# push_Button.net
KiCad netlist of a schematic drawn in EAGLE
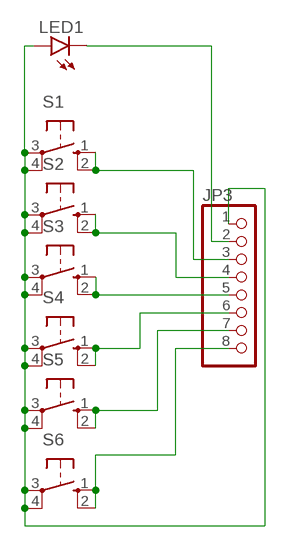
[diagram p0: schematic, sheet 1]

(export (version "E")
  (design (tool "Eeschema 10.0.6"))
  (components
    (comp (ref "JP3")
      (value "PINHD-1X8")
      (footprint "eagle-import:1X08")
      (libsource (lib "eagle-import") (part "PINHD-1X8"))
    )
    (comp (ref "LED1")
      (value "LED5MM")
      (footprint "eagle-import:LED5MM")
      (libsource (lib "eagle-import") (part "LED5MM"))
    )
    (comp (ref "S1")
      (value "10-XX")
      (footprint "eagle-import:B3F-10XX")
      (fields (field (name "MPN") "B3F-1000"))
      (libsource (lib "eagle-import") (part "10-XX"))
    )
    (comp (ref "S2")
      (value "10-XX")
      (footprint "eagle-import:B3F-10XX")
      (fields (field (name "MPN") "B3F-1000"))
      (libsource (lib "eagle-import") (part "10-XX"))
    )
    (comp (ref "S3")
      (value "10-XX")
      (footprint "eagle-import:B3F-10XX")
      (fields (field (name "MPN") "B3F-1000"))
      (libsource (lib "eagle-import") (part "10-XX"))
    )
    (comp (ref "S4")
      (value "10-XX")
      (footprint "eagle-import:B3F-10XX")
      (fields (field (name "MPN") "B3F-1000"))
      (libsource (lib "eagle-import") (part "10-XX"))
    )
    (comp (ref "S5")
      (value "10-XX")
      (footprint "eagle-import:B3F-10XX")
      (fields (field (name "MPN") "B3F-1000"))
      (libsource (lib "eagle-import") (part "10-XX"))
    )
    (comp (ref "S6")
      (value "10-XX")
      (footprint "eagle-import:B3F-10XX")
      (fields (field (name "MPN") "B3F-1000"))
      (libsource (lib "eagle-import") (part "10-XX"))
    )
  )
  (nets
    (net (code "1") (name "Net-(LED1-C)") (class "Default")
      (node (ref "JP3") (pin "2") (pinfunction "2_2") (pintype "passive"))
      (node (ref "LED1") (pin "K") (pinfunction "C_K") (pintype "passive"))
    )
    (net (code "2") (name "Net-(S1-P)") (class "Default")
      (node (ref "JP3") (pin "1") (pinfunction "1_1") (pintype "passive"))
      (node (ref "LED1") (pin "A") (pinfunction "A_A") (pintype "passive"))
      (node (ref "S1") (pin "3") (pinfunction "P_3") (pintype "passive"))
      (node (ref "S1") (pin "4") (pinfunction "P1_4") (pintype "passive"))
      (node (ref "S2") (pin "3") (pinfunction "P_3") (pintype "passive"))
      (node (ref "S2") (pin "4") (pinfunction "P1_4") (pintype "passive"))
      (node (ref "S3") (pin "3") (pinfunction "P_3") (pintype "passive"))
      (node (ref "S3") (pin "4") (pinfunction "P1_4") (pintype "passive"))
      (node (ref "S4") (pin "3") (pinfunction "P_3") (pintype "passive"))
      (node (ref "S4") (pin "4") (pinfunction "P1_4") (pintype "passive"))
      (node (ref "S5") (pin "3") (pinfunction "P_3") (pintype "passive"))
      (node (ref "S5") (pin "4") (pinfunction "P1_4") (pintype "passive"))
      (node (ref "S6") (pin "3") (pinfunction "P_3") (pintype "passive"))
      (node (ref "S6") (pin "4") (pinfunction "P1_4") (pintype "passive"))
    )
    (net (code "3") (name "Net-(S1-S)") (class "Default")
      (node (ref "JP3") (pin "3") (pinfunction "3_3") (pintype "passive"))
      (node (ref "S1") (pin "1") (pinfunction "S_1") (pintype "passive"))
      (node (ref "S1") (pin "2") (pinfunction "S1_2") (pintype "passive"))
    )
    (net (code "4") (name "Net-(S2-S)") (class "Default")
      (node (ref "JP3") (pin "4") (pinfunction "4_4") (pintype "passive"))
      (node (ref "S2") (pin "1") (pinfunction "S_1") (pintype "passive"))
      (node (ref "S2") (pin "2") (pinfunction "S1_2") (pintype "passive"))
    )
    (net (code "5") (name "Net-(S3-S)") (class "Default")
      (node (ref "JP3") (pin "5") (pinfunction "5_5") (pintype "passive"))
      (node (ref "S3") (pin "1") (pinfunction "S_1") (pintype "passive"))
      (node (ref "S3") (pin "2") (pinfunction "S1_2") (pintype "passive"))
    )
    (net (code "6") (name "Net-(S4-S)") (class "Default")
      (node (ref "JP3") (pin "6") (pinfunction "6_6") (pintype "passive"))
      (node (ref "S4") (pin "1") (pinfunction "S_1") (pintype "passive"))
      (node (ref "S4") (pin "2") (pinfunction "S1_2") (pintype "passive"))
    )
    (net (code "7") (name "Net-(S5-S)") (class "Default")
      (node (ref "JP3") (pin "7") (pinfunction "7_7") (pintype "passive"))
      (node (ref "S5") (pin "1") (pinfunction "S_1") (pintype "passive"))
      (node (ref "S5") (pin "2") (pinfunction "S1_2") (pintype "passive"))
    )
    (net (code "8") (name "Net-(S6-S)") (class "Default")
      (node (ref "JP3") (pin "8") (pinfunction "8_8") (pintype "passive"))
      (node (ref "S6") (pin "1") (pinfunction "S_1") (pintype "passive"))
      (node (ref "S6") (pin "2") (pinfunction "S1_2") (pintype "passive"))
    )
  )
)
